# Adafruit_Feather_RP4020_rev_B.net
KiCad netlist of a schematic drawn in EAGLE
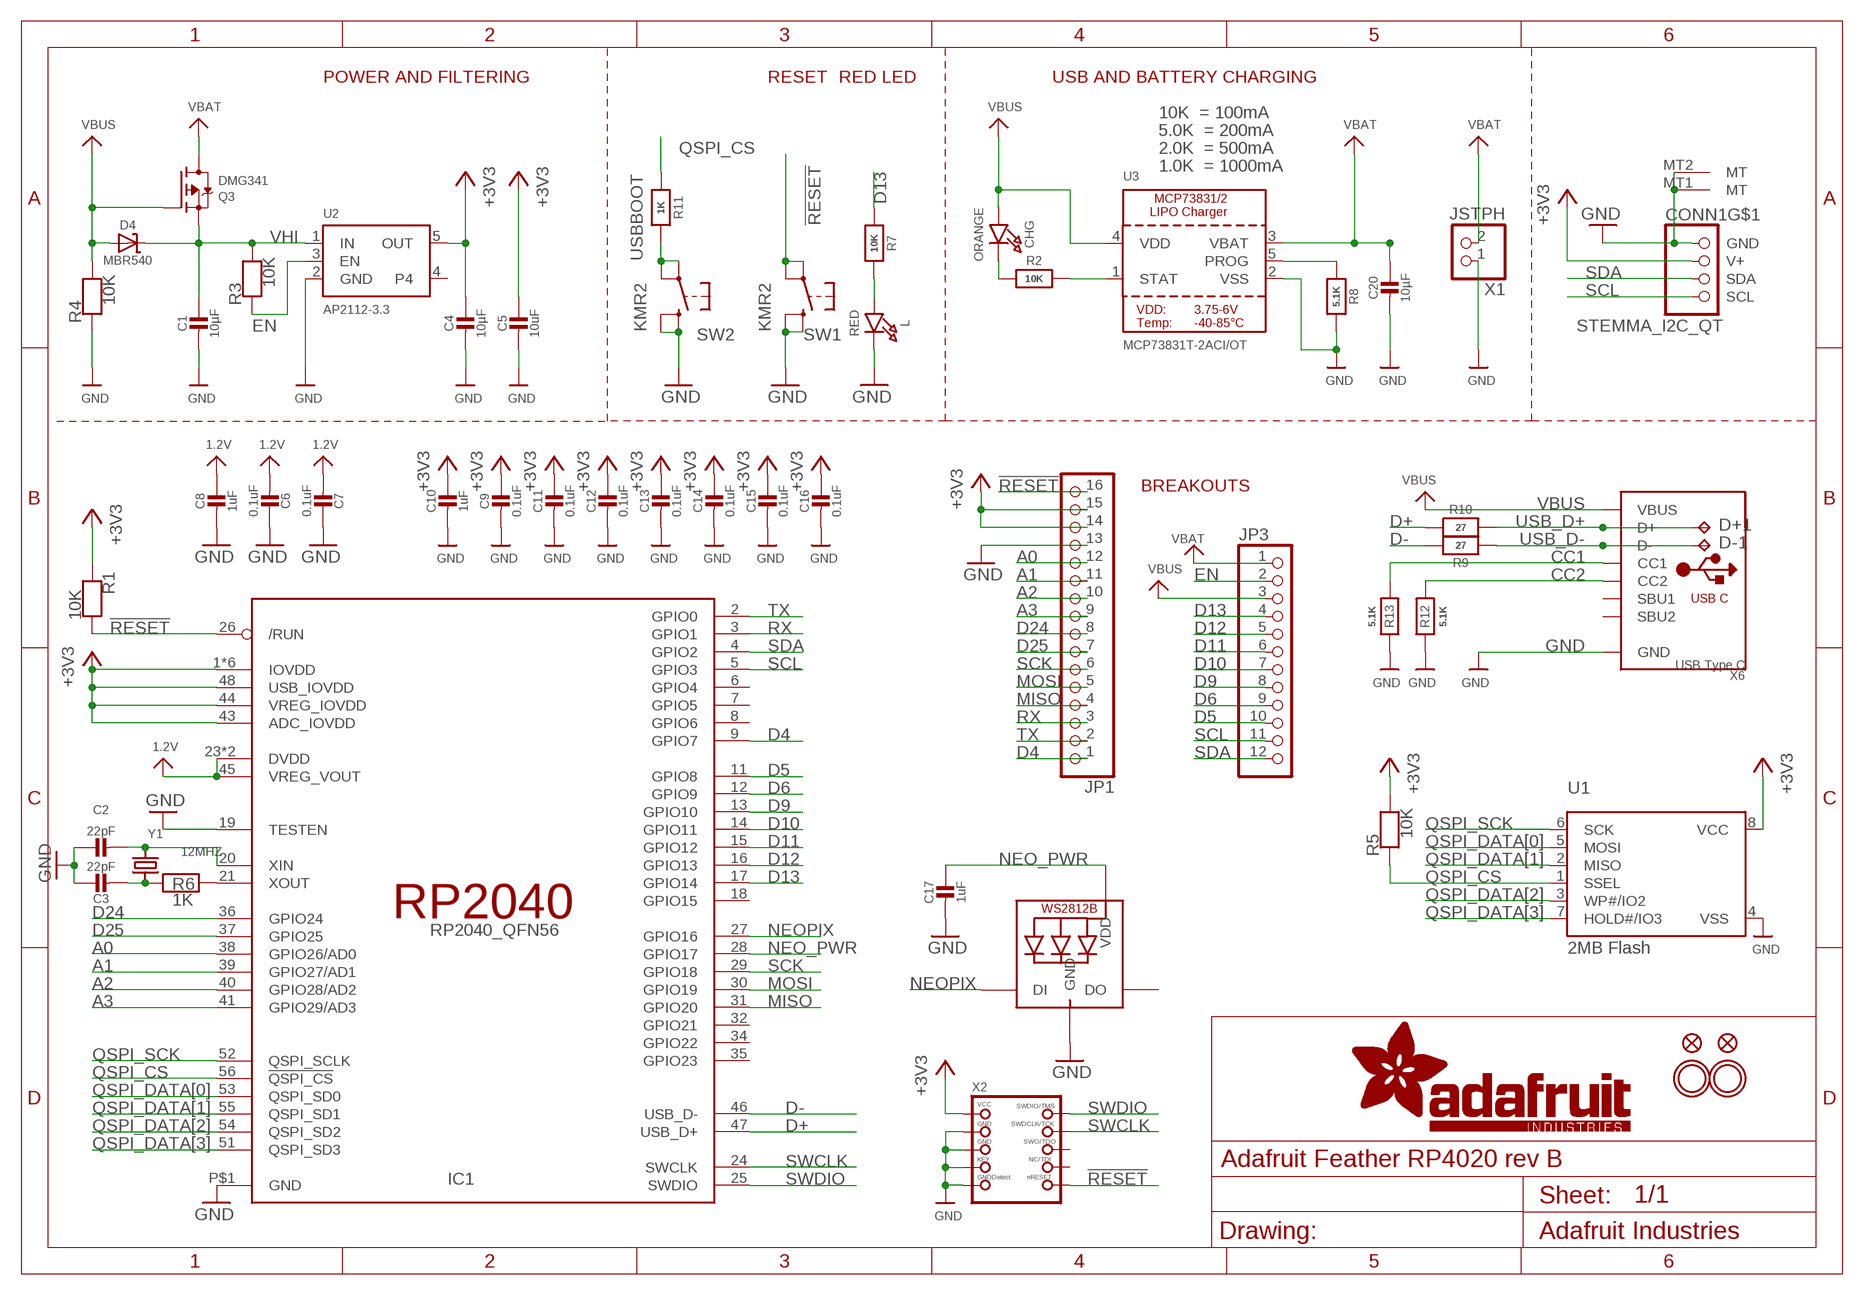
[diagram p0: schematic, sheet 1]

(export (version "E")
  (design (tool "Eeschema 10.0.6"))
  (components
    (comp (ref "C1")
      (value "10µF")
      (footprint "eagle-import:0805-NO")
      (libsource (lib "eagle-import") (part "CAP_CERAMIC0805-NOOUTLINE"))
    )
    (comp (ref "C2")
      (value "22pF")
      (footprint "eagle-import:0603-NO")
      (libsource (lib "eagle-import") (part "CAP_CERAMIC0603_NO"))
    )
    (comp (ref "C3")
      (value "22pF")
      (footprint "eagle-import:0603-NO")
      (libsource (lib "eagle-import") (part "CAP_CERAMIC0603_NO"))
    )
    (comp (ref "C4")
      (value "10µF")
      (footprint "eagle-import:0805-NO")
      (fields (field (name "REV") "A"))
      (libsource (lib "eagle-import") (part "CAP_CERAMIC0805-NOOUTLINE"))
    )
    (comp (ref "C5")
      (value "10uF")
      (footprint "eagle-import:0805-NO")
      (libsource (lib "eagle-import") (part "CAP_CERAMIC0805-NOOUTLINE"))
    )
    (comp (ref "C6")
      (value "0.1uF")
      (footprint "eagle-import:0603-NO")
      (libsource (lib "eagle-import") (part "CAP_CERAMIC0603_NO"))
    )
    (comp (ref "C7")
      (value "0.1uF")
      (footprint "eagle-import:0603-NO")
      (libsource (lib "eagle-import") (part "CAP_CERAMIC0603_NO"))
    )
    (comp (ref "C8")
      (value "1uF")
      (footprint "eagle-import:0603-NO")
      (libsource (lib "eagle-import") (part "CAP_CERAMIC0603_NO"))
    )
    (comp (ref "C9")
      (value "0.1uF")
      (footprint "eagle-import:0603-NO")
      (libsource (lib "eagle-import") (part "CAP_CERAMIC0603_NO"))
    )
    (comp (ref "C10")
      (value "1uF")
      (footprint "eagle-import:0603-NO")
      (libsource (lib "eagle-import") (part "CAP_CERAMIC0603_NO"))
    )
    (comp (ref "C11")
      (value "0.1uF")
      (footprint "eagle-import:0603-NO")
      (libsource (lib "eagle-import") (part "CAP_CERAMIC0603_NO"))
    )
    (comp (ref "C12")
      (value "0.1uF")
      (footprint "eagle-import:0603-NO")
      (libsource (lib "eagle-import") (part "CAP_CERAMIC0603_NO"))
    )
    (comp (ref "C13")
      (value "0.1uF")
      (footprint "eagle-import:0603-NO")
      (libsource (lib "eagle-import") (part "CAP_CERAMIC0603_NO"))
    )
    (comp (ref "C14")
      (value "0.1uF")
      (footprint "eagle-import:0603-NO")
      (libsource (lib "eagle-import") (part "CAP_CERAMIC0603_NO"))
    )
    (comp (ref "C15")
      (value "0.1uF")
      (footprint "eagle-import:0603-NO")
      (libsource (lib "eagle-import") (part "CAP_CERAMIC0603_NO"))
    )
    (comp (ref "C16")
      (value "0.1uF")
      (footprint "eagle-import:0603-NO")
      (libsource (lib "eagle-import") (part "CAP_CERAMIC0603_NO"))
    )
    (comp (ref "C17")
      (value "1uF")
      (footprint "eagle-import:0603-NO")
      (libsource (lib "eagle-import") (part "CAP_CERAMIC0603_NO"))
    )
    (comp (ref "C20")
      (value "10µF")
      (footprint "eagle-import:0805-NO")
      (libsource (lib "eagle-import") (part "CAP_CERAMIC0805-NOOUTLINE"))
    )
    (comp (ref "CHG")
      (value "ORANGE")
      (footprint "eagle-import:CHIPLED_0603_NOOUTLINE")
      (libsource (lib "eagle-import") (part "LED0603_NOOUTLINE"))
    )
    (comp (ref "CONN1")
      (value "STEMMA_I2C_QT")
      (footprint "eagle-import:JST_SH4")
      (libsource (lib "eagle-import") (part "STEMMA_I2C_QT"))
    )
    (comp (ref "D+1")
      (value "TPB1,27")
      (footprint "eagle-import:B1,27")
      (libsource (lib "eagle-import") (part "TPB1,27"))
    )
    (comp (ref "D-1")
      (value "TPB1,27")
      (footprint "eagle-import:B1,27")
      (libsource (lib "eagle-import") (part "TPB1,27"))
    )
    (comp (ref "D4")
      (value "MBR540")
      (footprint "eagle-import:SOD-123")
      (libsource (lib "eagle-import") (part "DIODE-SCHOTTKYSOD-123"))
    )
    (comp (ref "IC1")
      (value "RP2040_QFN56")
      (footprint "eagle-import:QFN56_7MM_REDUCEDEPAD")
      (libsource (lib "eagle-import") (part "RP2040_QFN56"))
    )
    (comp (ref "JP1")
      (value "HEADER-1X16ROUND")
      (footprint "eagle-import:1X16_ROUND")
      (libsource (lib "eagle-import") (part "HEADER-1X16ROUND"))
    )
    (comp (ref "JP3")
      (value "HEADER-1X12")
      (footprint "eagle-import:1X12_ROUND")
      (libsource (lib "eagle-import") (part "HEADER-1X12"))
    )
    (comp (ref "L")
      (value "RED")
      (footprint "eagle-import:CHIPLED_0603_NOOUTLINE")
      (libsource (lib "eagle-import") (part "LED0603_NOOUTLINE"))
    )
    (comp (ref "LED1")
      (value "WS2812B3535")
      (footprint "eagle-import:LED3535")
      (libsource (lib "eagle-import") (part "WS2812B3535"))
    )
    (comp (ref "Q3")
      (value "DMG341")
      (footprint "eagle-import:SOT23-R")
      (libsource (lib "eagle-import") (part "MOSFET-P"))
    )
    (comp (ref "R1")
      (value "10K")
      (footprint "eagle-import:0603-NO")
      (libsource (lib "eagle-import") (part "RESISTOR_0603_NOOUT"))
    )
    (comp (ref "R2")
      (value "10K")
      (footprint "eagle-import:0603-NO")
      (libsource (lib "eagle-import") (part "RESISTOR_0603_NOOUT"))
    )
    (comp (ref "R3")
      (value "10K")
      (footprint "eagle-import:0603-NO")
      (libsource (lib "eagle-import") (part "RESISTOR_0603_NOOUT"))
    )
    (comp (ref "R4")
      (value "10K")
      (footprint "eagle-import:0603-NO")
      (libsource (lib "eagle-import") (part "RESISTOR_0603_NOOUT"))
    )
    (comp (ref "R5")
      (value "10K")
      (footprint "eagle-import:0603-NO")
      (libsource (lib "eagle-import") (part "RESISTOR_0603_NOOUT"))
    )
    (comp (ref "R6")
      (value "1K")
      (footprint "eagle-import:0603-NO")
      (libsource (lib "eagle-import") (part "RESISTOR_0603_NOOUT"))
    )
    (comp (ref "R7")
      (value "10K")
      (footprint "eagle-import:0603-NO")
      (libsource (lib "eagle-import") (part "RESISTOR_0603_NOOUT"))
    )
    (comp (ref "R8")
      (value "5.1K")
      (footprint "eagle-import:0603-NO")
      (libsource (lib "eagle-import") (part "RESISTOR_0603_NOOUT"))
    )
    (comp (ref "R9")
      (value "27")
      (footprint "eagle-import:0603-NO")
      (libsource (lib "eagle-import") (part "RESISTOR_0603_NOOUT"))
    )
    (comp (ref "R10")
      (value "27")
      (footprint "eagle-import:0603-NO")
      (libsource (lib "eagle-import") (part "RESISTOR_0603_NOOUT"))
    )
    (comp (ref "R11")
      (value "1K")
      (footprint "eagle-import:0603-NO")
      (libsource (lib "eagle-import") (part "RESISTOR_0603_NOOUT"))
    )
    (comp (ref "R12")
      (value "5.1K")
      (footprint "eagle-import:0603-NO")
      (libsource (lib "eagle-import") (part "RESISTOR_0603_NOOUT"))
    )
    (comp (ref "R13")
      (value "5.1K")
      (footprint "eagle-import:0603-NO")
      (libsource (lib "eagle-import") (part "RESISTOR_0603_NOOUT"))
    )
    (comp (ref "SW1")
      (value "KMR2")
      (footprint "eagle-import:BTN_KMR2_4.6X2.8")
      (libsource (lib "eagle-import") (part "SWITCH_TACT_SMT4.6X2.8"))
    )
    (comp (ref "SW2")
      (value "KMR2")
      (footprint "eagle-import:BTN_KMR2_4.6X2.8")
      (libsource (lib "eagle-import") (part "SWITCH_TACT_SMT4.6X2.8"))
    )
    (comp (ref "U$31")
      (value "MOUNTINGHOLE2.5")
      (footprint "eagle-import:MOUNTINGHOLE_2.5_PLATED")
      (libsource (lib "eagle-import") (part "MOUNTINGHOLE2.5"))
    )
    (comp (ref "U$32")
      (value "MOUNTINGHOLE2.5")
      (footprint "eagle-import:MOUNTINGHOLE_2.5_PLATED")
      (libsource (lib "eagle-import") (part "MOUNTINGHOLE2.5"))
    )
    (comp (ref "U$34")
      (value "FIDUCIAL_1MM")
      (footprint "eagle-import:FIDUCIAL_1MM")
      (libsource (lib "eagle-import") (part "FIDUCIAL_1MM"))
    )
    (comp (ref "U$35")
      (value "FIDUCIAL_1MM")
      (footprint "eagle-import:FIDUCIAL_1MM")
      (libsource (lib "eagle-import") (part "FIDUCIAL_1MM"))
    )
    (comp (ref "U1")
      (value "2MB Flash")
      (footprint "eagle-import:SOIC8_208MIL")
      (libsource (lib "eagle-import") (part "SPIFLASH_8PIN208MIL"))
    )
    (comp (ref "U2")
      (value "AP2112-3.3")
      (footprint "eagle-import:SOT23-5@1")
      (libsource (lib "eagle-import") (part "VREG_SOT23-5"))
    )
    (comp (ref "U3")
      (value "MCP73831T-2ACI/OT")
      (footprint "eagle-import:SOT23-5")
      (libsource (lib "eagle-import") (part "MCP73831/2"))
    )
    (comp (ref "X1")
      (value "JSTPH")
      (footprint "eagle-import:JSTPH2_BATT")
      (libsource (lib "eagle-import") (part "CON_JST_PH_2PIN_BATT"))
    )
    (comp (ref "X2")
      (value "JTAG-CORTEXBOXPOSTS")
      (footprint "eagle-import:2X05_1.27MM_BOX_POSTS")
      (libsource (lib "eagle-import") (part "JTAG-CORTEXBOXPOSTS"))
    )
    (comp (ref "X6")
      (value "USB Type C")
      (footprint "eagle-import:USB_C_CUSB31-CFM2AX-01-X")
      (libsource (lib "eagle-import") (part "USB_C"))
    )
    (comp (ref "Y1")
      (value "12MHZ")
      (footprint "eagle-import:CRYSTAL_2.5X2")
      (libsource (lib "eagle-import") (part "CRYSTAL2.5X2.0"))
    )
  )
  (nets
    (net (code "1") (name "+3V3") (class "Default")
      (node (ref "C10") (pin "1") (pinfunction "1_1") (pintype "passive"))
      (node (ref "C11") (pin "1") (pinfunction "1_1") (pintype "passive"))
      (node (ref "C12") (pin "1") (pinfunction "1_1") (pintype "passive"))
      (node (ref "C13") (pin "1") (pinfunction "1_1") (pintype "passive"))
      (node (ref "C14") (pin "1") (pinfunction "1_1") (pintype "passive"))
      (node (ref "C15") (pin "1") (pinfunction "1_1") (pintype "passive"))
      (node (ref "C16") (pin "1") (pinfunction "1_1") (pintype "passive"))
      (node (ref "C4") (pin "1") (pinfunction "1_1") (pintype "passive"))
      (node (ref "C5") (pin "1") (pinfunction "1_1") (pintype "passive"))
      (node (ref "C9") (pin "1") (pinfunction "1_1") (pintype "passive"))
      (node (ref "CONN1") (pin "2") (pinfunction "V+_2") (pintype "passive"))
      (node (ref "IC1") (pin "1") (pinfunction "IOVDD_1") (pintype "power_in"))
      (node (ref "IC1") (pin "10") (pinfunction "IOVDD_10") (pintype "power_in"))
      (node (ref "IC1") (pin "22") (pinfunction "IOVDD_22") (pintype "power_in"))
      (node (ref "IC1") (pin "33") (pinfunction "IOVDD_33") (pintype "power_in"))
      (node (ref "IC1") (pin "42") (pinfunction "IOVDD_42") (pintype "power_in"))
      (node (ref "IC1") (pin "43") (pinfunction "ADC_IOVDD_43") (pintype "power_in"))
      (node (ref "IC1") (pin "44") (pinfunction "VREG_IOVDD_44") (pintype "power_in"))
      (node (ref "IC1") (pin "48") (pinfunction "USB_IOVDD_48") (pintype "power_in"))
      (node (ref "IC1") (pin "49") (pinfunction "IOVDD_49") (pintype "power_in"))
      (node (ref "JP1") (pin "14") (pinfunction "14_14") (pintype "passive"))
      (node (ref "JP1") (pin "15") (pinfunction "15_15") (pintype "passive"))
      (node (ref "R1") (pin "1") (pinfunction "1_1") (pintype "passive"))
      (node (ref "R5") (pin "2") (pinfunction "2_2") (pintype "passive"))
      (node (ref "U1") (pin "8") (pinfunction "VCC_8") (pintype "bidirectional"))
      (node (ref "U2") (pin "5") (pinfunction "OUT_5") (pintype "power_in"))
      (node (ref "X2") (pin "1") (pinfunction "VCC_1") (pintype "power_in"))
    )
    (net (code "2") (name "/A0") (class "Default")
      (node (ref "IC1") (pin "38") (pinfunction "GPIO26/AD0_38") (pintype "bidirectional"))
      (node (ref "JP1") (pin "12") (pinfunction "12_12") (pintype "passive"))
    )
    (net (code "3") (name "/A1") (class "Default")
      (node (ref "IC1") (pin "39") (pinfunction "GPIO27/AD1_39") (pintype "bidirectional"))
      (node (ref "JP1") (pin "11") (pinfunction "11_11") (pintype "passive"))
    )
    (net (code "4") (name "/A2") (class "Default")
      (node (ref "IC1") (pin "40") (pinfunction "GPIO28/AD2_40") (pintype "bidirectional"))
      (node (ref "JP1") (pin "10") (pinfunction "10_10") (pintype "passive"))
    )
    (net (code "5") (name "/A3") (class "Default")
      (node (ref "IC1") (pin "41") (pinfunction "GPIO29/AD3_41") (pintype "bidirectional"))
      (node (ref "JP1") (pin "9") (pinfunction "9_9") (pintype "passive"))
    )
    (net (code "6") (name "/CC1") (class "Default")
      (node (ref "R13") (pin "2") (pinfunction "2_2") (pintype "passive"))
      (node (ref "X6") (pin "A5") (pinfunction "CC1_A5") (pintype "bidirectional"))
    )
    (net (code "7") (name "/CC2") (class "Default")
      (node (ref "R12") (pin "2") (pinfunction "2_2") (pintype "passive"))
      (node (ref "X6") (pin "B5") (pinfunction "CC2_B5") (pintype "bidirectional"))
    )
    (net (code "8") (name "/D+") (class "Default")
      (node (ref "IC1") (pin "47") (pinfunction "USB_D+_47") (pintype "bidirectional"))
      (node (ref "R10") (pin "2") (pinfunction "2_2") (pintype "passive"))
    )
    (net (code "9") (name "/D-") (class "Default")
      (node (ref "IC1") (pin "46") (pinfunction "USB_D-_46") (pintype "bidirectional"))
      (node (ref "R9") (pin "2") (pinfunction "2_2") (pintype "passive"))
    )
    (net (code "10") (name "/D4") (class "Default")
      (node (ref "IC1") (pin "9") (pinfunction "GPIO7_9") (pintype "bidirectional"))
      (node (ref "JP1") (pin "1") (pinfunction "1_1") (pintype "passive"))
    )
    (net (code "11") (name "/D5") (class "Default")
      (node (ref "IC1") (pin "11") (pinfunction "GPIO8_11") (pintype "bidirectional"))
      (node (ref "JP3") (pin "10") (pinfunction "10_10") (pintype "passive"))
    )
    (net (code "12") (name "/D6") (class "Default")
      (node (ref "IC1") (pin "12") (pinfunction "GPIO9_12") (pintype "bidirectional"))
      (node (ref "JP3") (pin "9") (pinfunction "9_9") (pintype "passive"))
    )
    (net (code "13") (name "/D9") (class "Default")
      (node (ref "IC1") (pin "13") (pinfunction "GPIO10_13") (pintype "bidirectional"))
      (node (ref "JP3") (pin "8") (pinfunction "8_8") (pintype "passive"))
    )
    (net (code "14") (name "/D10") (class "Default")
      (node (ref "IC1") (pin "14") (pinfunction "GPIO11_14") (pintype "bidirectional"))
      (node (ref "JP3") (pin "7") (pinfunction "7_7") (pintype "passive"))
    )
    (net (code "15") (name "/D11") (class "Default")
      (node (ref "IC1") (pin "15") (pinfunction "GPIO12_15") (pintype "bidirectional"))
      (node (ref "JP3") (pin "6") (pinfunction "6_6") (pintype "passive"))
    )
    (net (code "16") (name "/D12") (class "Default")
      (node (ref "IC1") (pin "16") (pinfunction "GPIO13_16") (pintype "bidirectional"))
      (node (ref "JP3") (pin "5") (pinfunction "5_5") (pintype "passive"))
    )
    (net (code "17") (name "/D13") (class "Default")
      (node (ref "IC1") (pin "17") (pinfunction "GPIO14_17") (pintype "bidirectional"))
      (node (ref "JP3") (pin "4") (pinfunction "4_4") (pintype "passive"))
      (node (ref "R7") (pin "1") (pinfunction "1_1") (pintype "passive"))
    )
    (net (code "18") (name "/D24") (class "Default")
      (node (ref "IC1") (pin "36") (pinfunction "GPIO24_36") (pintype "bidirectional"))
      (node (ref "JP1") (pin "8") (pinfunction "8_8") (pintype "passive"))
    )
    (net (code "19") (name "/D25") (class "Default")
      (node (ref "IC1") (pin "37") (pinfunction "GPIO25_37") (pintype "bidirectional"))
      (node (ref "JP1") (pin "7") (pinfunction "7_7") (pintype "passive"))
    )
    (net (code "20") (name "/EN") (class "Default")
      (node (ref "JP3") (pin "2") (pinfunction "2_2") (pintype "passive"))
      (node (ref "R3") (pin "1") (pinfunction "1_1") (pintype "passive"))
      (node (ref "U2") (pin "3") (pinfunction "EN_3") (pintype "input"))
    )
    (net (code "21") (name "/MISO") (class "Default")
      (node (ref "IC1") (pin "31") (pinfunction "GPIO20_31") (pintype "bidirectional"))
      (node (ref "JP1") (pin "4") (pinfunction "4_4") (pintype "passive"))
    )
    (net (code "22") (name "/MOSI") (class "Default")
      (node (ref "IC1") (pin "30") (pinfunction "GPIO19_30") (pintype "bidirectional"))
      (node (ref "JP1") (pin "5") (pinfunction "5_5") (pintype "passive"))
    )
    (net (code "23") (name "/NEOPIX") (class "Default")
      (node (ref "IC1") (pin "27") (pinfunction "GPIO16_27") (pintype "bidirectional"))
      (node (ref "LED1") (pin "1") (pinfunction "DI_1") (pintype "input"))
    )
    (net (code "24") (name "/NEO_PWR") (class "Default")
      (node (ref "C17") (pin "1") (pinfunction "1_1") (pintype "passive"))
      (node (ref "IC1") (pin "28") (pinfunction "GPIO17_28") (pintype "bidirectional"))
      (node (ref "LED1") (pin "2") (pinfunction "VDD_2") (pintype "power_in"))
    )
    (net (code "25") (name "/QSPI_CS") (class "Default")
      (node (ref "IC1") (pin "56") (pinfunction "~{QSPI_CS}_56") (pintype "bidirectional"))
      (node (ref "R11") (pin "1") (pinfunction "1_1") (pintype "passive"))
      (node (ref "R5") (pin "1") (pinfunction "1_1") (pintype "passive"))
      (node (ref "U1") (pin "1") (pinfunction "SSEL_1") (pintype "bidirectional"))
    )
    (net (code "26") (name "/QSPI_DATA[0]") (class "Default")
      (node (ref "IC1") (pin "53") (pinfunction "QSPI_SD0_53") (pintype "bidirectional"))
      (node (ref "U1") (pin "5") (pinfunction "MOSI_5") (pintype "bidirectional"))
    )
    (net (code "27") (name "/QSPI_DATA[1]") (class "Default")
      (node (ref "IC1") (pin "55") (pinfunction "QSPI_SD1_55") (pintype "bidirectional"))
      (node (ref "U1") (pin "2") (pinfunction "MISO_2") (pintype "bidirectional"))
    )
    (net (code "28") (name "/QSPI_DATA[2]") (class "Default")
      (node (ref "IC1") (pin "54") (pinfunction "QSPI_SD2_54") (pintype "bidirectional"))
      (node (ref "U1") (pin "3") (pinfunction "WP#/IO2_3") (pintype "bidirectional"))
    )
    (net (code "29") (name "/QSPI_DATA[3]") (class "Default")
      (node (ref "IC1") (pin "51") (pinfunction "QSPI_SD3_51") (pintype "bidirectional"))
      (node (ref "U1") (pin "7") (pinfunction "HOLD#/IO3_7") (pintype "bidirectional"))
    )
    (net (code "30") (name "/QSPI_SCK") (class "Default")
      (node (ref "IC1") (pin "52") (pinfunction "QSPI_SCLK_52") (pintype "bidirectional"))
      (node (ref "U1") (pin "6") (pinfunction "SCK_6") (pintype "bidirectional"))
    )
    (net (code "31") (name "/RX") (class "Default")
      (node (ref "IC1") (pin "3") (pinfunction "GPIO1_3") (pintype "bidirectional"))
      (node (ref "JP1") (pin "3") (pinfunction "3_3") (pintype "passive"))
    )
    (net (code "32") (name "/SCK") (class "Default")
      (node (ref "IC1") (pin "29") (pinfunction "GPIO18_29") (pintype "bidirectional"))
      (node (ref "JP1") (pin "6") (pinfunction "6_6") (pintype "passive"))
    )
    (net (code "33") (name "/SCL") (class "Default")
      (node (ref "CONN1") (pin "4") (pinfunction "SCL_4") (pintype "passive"))
      (node (ref "IC1") (pin "5") (pinfunction "GPIO3_5") (pintype "bidirectional"))
      (node (ref "JP3") (pin "11") (pinfunction "11_11") (pintype "passive"))
    )
    (net (code "34") (name "/SDA") (class "Default")
      (node (ref "CONN1") (pin "3") (pinfunction "SDA_3") (pintype "passive"))
      (node (ref "IC1") (pin "4") (pinfunction "GPIO2_4") (pintype "bidirectional"))
      (node (ref "JP3") (pin "12") (pinfunction "12_12") (pintype "passive"))
    )
    (net (code "35") (name "/SWCLK") (class "Default")
      (node (ref "IC1") (pin "24") (pinfunction "SWCLK_24") (pintype "bidirectional"))
      (node (ref "X2") (pin "4") (pinfunction "SWDCLK_4") (pintype "bidirectional"))
    )
    (net (code "36") (name "/SWDIO") (class "Default")
      (node (ref "IC1") (pin "25") (pinfunction "SWDIO_25") (pintype "bidirectional"))
      (node (ref "X2") (pin "2") (pinfunction "SWDIO_2") (pintype "bidirectional"))
    )
    (net (code "37") (name "/TX") (class "Default")
      (node (ref "IC1") (pin "2") (pinfunction "GPIO0_2") (pintype "bidirectional"))
      (node (ref "JP1") (pin "2") (pinfunction "2_2") (pintype "passive"))
    )
    (net (code "38") (name "/USBBOOT") (class "Default")
      (node (ref "R11") (pin "2") (pinfunction "2_2") (pintype "passive"))
      (node (ref "SW2") (pin "A") (pinfunction "P_A") (pintype "passive"))
      (node (ref "SW2") (pin "A'") (pinfunction "P1_A'") (pintype "passive"))
    )
    (net (code "39") (name "/USB_D+") (class "Default")
      (node (ref "D+1") (pin "TP") (pinfunction "TP_TP") (pintype "input"))
      (node (ref "R10") (pin "1") (pinfunction "1_1") (pintype "passive"))
      (node (ref "X6") (pin "A6") (pinfunction "D+_A6") (pintype "bidirectional"))
      (node (ref "X6") (pin "B6") (pinfunction "D+_B6") (pintype "bidirectional"))
    )
    (net (code "40") (name "/USB_D-") (class "Default")
      (node (ref "D-1") (pin "TP") (pinfunction "TP_TP") (pintype "input"))
      (node (ref "R9") (pin "1") (pinfunction "1_1") (pintype "passive"))
      (node (ref "X6") (pin "A7") (pinfunction "D-_A7") (pintype "bidirectional"))
      (node (ref "X6") (pin "B7") (pinfunction "D-_B7") (pintype "bidirectional"))
    )
    (net (code "41") (name "/VHI") (class "Default")
      (node (ref "C1") (pin "1") (pinfunction "1_1") (pintype "passive"))
      (node (ref "D4") (pin "C") (pinfunction "C_C") (pintype "passive"))
      (node (ref "Q3") (pin "2") (pinfunction "S_2") (pintype "passive"))
      (node (ref "R3") (pin "2") (pinfunction "2_2") (pintype "passive"))
      (node (ref "U2") (pin "1") (pinfunction "IN_1") (pintype "power_in"))
    )
    (net (code "42") (name "/~{RESET}") (class "Default")
      (node (ref "IC1") (pin "26") (pinfunction "/RUN_26") (pintype "bidirectional"))
      (node (ref "JP1") (pin "16") (pinfunction "16_16") (pintype "passive"))
      (node (ref "R1") (pin "2") (pinfunction "2_2") (pintype "passive"))
      (node (ref "SW1") (pin "A") (pinfunction "P_A") (pintype "passive"))
      (node (ref "SW1") (pin "A'") (pinfunction "P1_A'") (pintype "passive"))
      (node (ref "X2") (pin "10") (pinfunction "NRESET_10") (pintype "bidirectional"))
    )
    (net (code "43") (name "1.2V") (class "Default")
      (node (ref "C6") (pin "2") (pinfunction "2_2") (pintype "passive"))
      (node (ref "C7") (pin "2") (pinfunction "2_2") (pintype "passive"))
      (node (ref "C8") (pin "1") (pinfunction "1_1") (pintype "passive"))
      (node (ref "IC1") (pin "23") (pinfunction "DVDD_23") (pintype "power_in"))
      (node (ref "IC1") (pin "45") (pinfunction "VREG_VOUT_45") (pintype "power_in"))
      (node (ref "IC1") (pin "50") (pinfunction "DVDD_50") (pintype "power_in"))
    )
    (net (code "44") (name "GND") (class "Default")
      (node (ref "C1") (pin "2") (pinfunction "2_2") (pintype "passive"))
      (node (ref "C10") (pin "2") (pinfunction "2_2") (pintype "passive"))
      (node (ref "C11") (pin "2") (pinfunction "2_2") (pintype "passive"))
      (node (ref "C12") (pin "2") (pinfunction "2_2") (pintype "passive"))
      (node (ref "C13") (pin "2") (pinfunction "2_2") (pintype "passive"))
      (node (ref "C14") (pin "2") (pinfunction "2_2") (pintype "passive"))
      (node (ref "C15") (pin "2") (pinfunction "2_2") (pintype "passive"))
      (node (ref "C16") (pin "2") (pinfunction "2_2") (pintype "passive"))
      (node (ref "C17") (pin "2") (pinfunction "2_2") (pintype "passive"))
      (node (ref "C2") (pin "1") (pinfunction "1_1") (pintype "passive"))
      (node (ref "C20") (pin "2") (pinfunction "2_2") (pintype "passive"))
      (node (ref "C3") (pin "1") (pinfunction "1_1") (pintype "passive"))
      (node (ref "C4") (pin "2") (pinfunction "2_2") (pintype "passive"))
      (node (ref "C5") (pin "2") (pinfunction "2_2") (pintype "passive"))
      (node (ref "C6") (pin "1") (pinfunction "1_1") (pintype "passive"))
      (node (ref "C7") (pin "1") (pinfunction "1_1") (pintype "passive"))
      (node (ref "C8") (pin "2") (pinfunction "2_2") (pintype "passive"))
      (node (ref "C9") (pin "2") (pinfunction "2_2") (pintype "passive"))
      (node (ref "CONN1") (pin "1") (pinfunction "GND_1") (pintype "passive"))
      (node (ref "CONN1") (pin "MT1") (pinfunction "MT_MT1") (pintype "bidirectional"))
      (node (ref "CONN1") (pin "MT2") (pinfunction "MT_MT2") (pintype "bidirectional"))
      (node (ref "IC1") (pin "19") (pinfunction "TESTEN_19") (pintype "input"))
      (node (ref "IC1") (pin "P$1") (pinfunction "GND_P$1") (pintype "power_in"))
      (node (ref "JP1") (pin "13") (pinfunction "13_13") (pintype "passive"))
      (node (ref "L") (pin "C") (pinfunction "C_C") (pintype "passive"))
      (node (ref "LED1") (pin "4") (pinfunction "GND_4") (pintype "power_in"))
      (node (ref "R12") (pin "1") (pinfunction "1_1") (pintype "passive"))
      (node (ref "R13") (pin "1") (pinfunction "1_1") (pintype "passive"))
      (node (ref "R4") (pin "1") (pinfunction "1_1") (pintype "passive"))
      (node (ref "R8") (pin "2") (pinfunction "2_2") (pintype "passive"))
      (node (ref "SW1") (pin "B") (pinfunction "S_B") (pintype "passive"))
      (node (ref "SW1") (pin "B'") (pinfunction "S1_B'") (pintype "passive"))
      (node (ref "SW2") (pin "B") (pinfunction "S_B") (pintype "passive"))
      (node (ref "SW2") (pin "B'") (pinfunction "S1_B'") (pintype "passive"))
      (node (ref "U1") (pin "4") (pinfunction "VSS_4") (pintype "bidirectional"))
      (node (ref "U2") (pin "2") (pinfunction "GND_2") (pintype "power_in"))
      (node (ref "U3") (pin "2") (pinfunction "VSS_2") (pintype "power_in"))
      (node (ref "X1") (pin "1") (pinfunction "1_1") (pintype "passive"))
      (node (ref "X2") (pin "3") (pinfunction "GND_3") (pintype "power_in"))
      (node (ref "X2") (pin "5") (pinfunction "GND_5") (pintype "power_in"))
      (node (ref "X2") (pin "7") (pinfunction "KEY_7") (pintype "bidirectional"))
      (node (ref "X2") (pin "9") (pinfunction "GNDDETECT_9") (pintype "bidirectional"))
      (node (ref "X6") (pin "A1B12") (pinfunction "GND_A1B12") (pintype "power_in"))
      (node (ref "X6") (pin "B1A12") (pinfunction "GND_B1A12") (pintype "power_in"))
    )
    (net (code "45") (name "Net-(C3-Pad2)") (class "Default")
      (node (ref "C3") (pin "2") (pinfunction "2_2") (pintype "passive"))
      (node (ref "R6") (pin "1") (pinfunction "1_1") (pintype "passive"))
      (node (ref "Y1") (pin "1") (pinfunction "1_1") (pintype "passive"))
    )
    (net (code "46") (name "Net-(CHG-PadC)") (class "Default")
      (node (ref "CHG") (pin "C") (pinfunction "C_C") (pintype "passive"))
      (node (ref "R2") (pin "1") (pinfunction "1_1") (pintype "passive"))
    )
    (net (code "47") (name "Net-(IC1-XIN)") (class "Default")
      (node (ref "C2") (pin "2") (pinfunction "2_2") (pintype "passive"))
      (node (ref "IC1") (pin "20") (pinfunction "XIN_20") (pintype "input"))
      (node (ref "Y1") (pin "3") (pinfunction "2_3") (pintype "passive"))
    )
    (net (code "48") (name "Net-(IC1-XOUT)") (class "Default")
      (node (ref "IC1") (pin "21") (pinfunction "XOUT_21") (pintype "output"))
      (node (ref "R6") (pin "2") (pinfunction "2_2") (pintype "passive"))
    )
    (net (code "49") (name "Net-(L-PadA)") (class "Default")
      (node (ref "L") (pin "A") (pinfunction "A_A") (pintype "passive"))
      (node (ref "R7") (pin "2") (pinfunction "2_2") (pintype "passive"))
    )
    (net (code "50") (name "Net-(U3-PROG)") (class "Default")
      (node (ref "R8") (pin "1") (pinfunction "1_1") (pintype "passive"))
      (node (ref "U3") (pin "5") (pinfunction "PROG_5") (pintype "input"))
    )
    (net (code "51") (name "Net-(U3-STAT)") (class "Default")
      (node (ref "R2") (pin "2") (pinfunction "2_2") (pintype "passive"))
      (node (ref "U3") (pin "1") (pinfunction "STAT_1") (pintype "output"))
    )
    (net (code "52") (name "VBAT") (class "Default")
      (node (ref "C20") (pin "1") (pinfunction "1_1") (pintype "passive"))
      (node (ref "JP3") (pin "1") (pinfunction "1_1") (pintype "passive"))
      (node (ref "Q3") (pin "3") (pinfunction "D_3") (pintype "passive"))
      (node (ref "U3") (pin "3") (pinfunction "VBAT_3") (pintype "power_in"))
      (node (ref "X1") (pin "2") (pinfunction "2_2") (pintype "passive"))
    )
    (net (code "53") (name "VBUS") (class "Default")
      (node (ref "CHG") (pin "A") (pinfunction "A_A") (pintype "passive"))
      (node (ref "D4") (pin "A") (pinfunction "A_A") (pintype "passive"))
      (node (ref "JP3") (pin "3") (pinfunction "3_3") (pintype "passive"))
      (node (ref "Q3") (pin "1") (pinfunction "G_1") (pintype "passive"))
      (node (ref "R4") (pin "2") (pinfunction "2_2") (pintype "passive"))
      (node (ref "U3") (pin "4") (pinfunction "VDD_4") (pintype "power_in"))
      (node (ref "X6") (pin "A4B9") (pinfunction "VBUS_A4B9") (pintype "power_in"))
      (node (ref "X6") (pin "B4A9") (pinfunction "VBUS_B4A9") (pintype "power_in"))
    )
    (net (code "54") (name "unconnected-(IC1-GPIO4-Pad6)") (class "Default")
      (node (ref "IC1") (pin "6") (pinfunction "GPIO4_6") (pintype "bidirectional"))
    )
    (net (code "55") (name "unconnected-(IC1-GPIO5-Pad7)") (class "Default")
      (node (ref "IC1") (pin "7") (pinfunction "GPIO5_7") (pintype "bidirectional"))
    )
    (net (code "56") (name "unconnected-(IC1-GPIO6-Pad8)") (class "Default")
      (node (ref "IC1") (pin "8") (pinfunction "GPIO6_8") (pintype "bidirectional"))
    )
    (net (code "57") (name "unconnected-(IC1-GPIO15-Pad18)") (class "Default")
      (node (ref "IC1") (pin "18") (pinfunction "GPIO15_18") (pintype "bidirectional"))
    )
    (net (code "58") (name "unconnected-(IC1-GPIO21-Pad32)") (class "Default")
      (node (ref "IC1") (pin "32") (pinfunction "GPIO21_32") (pintype "bidirectional"))
    )
    (net (code "59") (name "unconnected-(IC1-GPIO22-Pad34)") (class "Default")
      (node (ref "IC1") (pin "34") (pinfunction "GPIO22_34") (pintype "bidirectional"))
    )
    (net (code "60") (name "unconnected-(IC1-GPIO23-Pad35)") (class "Default")
      (node (ref "IC1") (pin "35") (pinfunction "GPIO23_35") (pintype "bidirectional"))
    )
    (net (code "61") (name "unconnected-(LED1-DO-Pad3)") (class "Default")
      (node (ref "LED1") (pin "3") (pinfunction "DO_3") (pintype "output"))
    )
    (net (code "62") (name "unconnected-(U2-P4-Pad4)") (class "Default")
      (node (ref "U2") (pin "4") (pinfunction "P4_4") (pintype "bidirectional"))
    )
    (net (code "63") (name "unconnected-(X2-SWO-Pad6)") (class "Default")
      (node (ref "X2") (pin "6") (pinfunction "SWO_6") (pintype "bidirectional"))
    )
    (net (code "64") (name "unconnected-(X2-TDI-Pad8)") (class "Default")
      (node (ref "X2") (pin "8") (pinfunction "TDI_8") (pintype "bidirectional"))
    )
    (net (code "65") (name "unconnected-(X6-SBU1-PadA8)") (class "Default")
      (node (ref "X6") (pin "A8") (pinfunction "SBU1_A8") (pintype "bidirectional"))
    )
    (net (code "66") (name "unconnected-(X6-SBU2-PadB8)") (class "Default")
      (node (ref "X6") (pin "B8") (pinfunction "SBU2_B8") (pintype "bidirectional"))
    )
  )
)
